# Connectors.net
KiCad netlist of a schematic drawn in Altium Designer
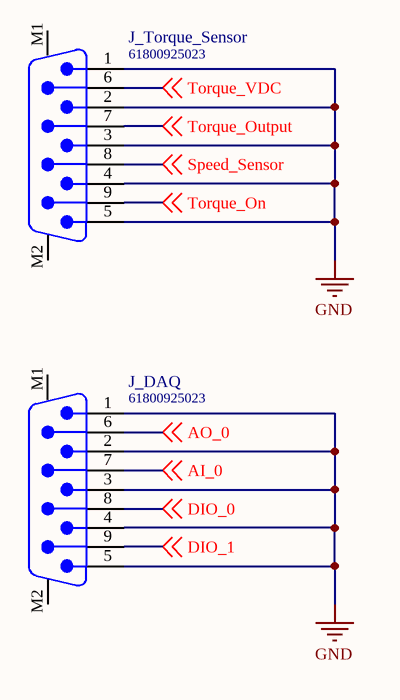
[diagram p0: Connectors.SchDoc]

(export (version "E")
  (design (tool "Eeschema 10.0.6"))
  (components
    (comp (ref "J_DAQ")
      (value "61800925023")
      (footprint "61800925023")
      (description "Male PCB Connector WR-DSUB, Vertical, 9 pins")
      (fields (field (name "MANUFACTURER") "Wurth Elektronik") (field (name "PUBLISHER") "WurthElektronik"))
      (libsource (lib "Altium Content Vault") (part "WE-CN-2S-2M-D9"))
    )
    (comp (ref "J_Torque_Sensor")
      (value "61800925023")
      (footprint "61800925023")
      (description "Male PCB Connector WR-DSUB, Vertical, 9 pins")
      (fields (field (name "MANUFACTURER") "Wurth Elektronik") (field (name "PUBLISHER") "WurthElektronik"))
      (libsource (lib "Altium Content Vault") (part "WE-CN-2S-2M-D9"))
    )
  )
  (nets
    (net (code "1") (name "AI_0") (class "Default")
      (node (ref "J_DAQ") (pin "7") (pinfunction "7_7") (pintype "passive"))
    )
    (net (code "2") (name "AO_0") (class "Default")
      (node (ref "J_DAQ") (pin "6") (pinfunction "6_6") (pintype "passive"))
    )
    (net (code "3") (name "DIO_0") (class "Default")
      (node (ref "J_DAQ") (pin "8") (pinfunction "8_8") (pintype "passive"))
    )
    (net (code "4") (name "DIO_1") (class "Default")
      (node (ref "J_DAQ") (pin "9") (pinfunction "9_9") (pintype "passive"))
    )
    (net (code "5") (name "GND") (class "Default")
      (node (ref "J_DAQ") (pin "1") (pinfunction "1_1") (pintype "passive"))
      (node (ref "J_DAQ") (pin "2") (pinfunction "2_2") (pintype "passive"))
      (node (ref "J_DAQ") (pin "3") (pinfunction "3_3") (pintype "passive"))
      (node (ref "J_DAQ") (pin "4") (pinfunction "4_4") (pintype "passive"))
      (node (ref "J_DAQ") (pin "5") (pinfunction "5_5") (pintype "passive"))
      (node (ref "J_Torque_Sensor") (pin "1") (pinfunction "1_1") (pintype "passive"))
      (node (ref "J_Torque_Sensor") (pin "2") (pinfunction "2_2") (pintype "passive"))
      (node (ref "J_Torque_Sensor") (pin "3") (pinfunction "3_3") (pintype "passive"))
      (node (ref "J_Torque_Sensor") (pin "4") (pinfunction "4_4") (pintype "passive"))
      (node (ref "J_Torque_Sensor") (pin "5") (pinfunction "5_5") (pintype "passive"))
    )
    (net (code "6") (name "Speed_Sensor") (class "Default")
      (node (ref "J_Torque_Sensor") (pin "8") (pinfunction "8_8") (pintype "passive"))
    )
    (net (code "7") (name "Torque_On") (class "Default")
      (node (ref "J_Torque_Sensor") (pin "9") (pinfunction "9_9") (pintype "passive"))
    )
    (net (code "8") (name "Torque_Output") (class "Default")
      (node (ref "J_Torque_Sensor") (pin "7") (pinfunction "7_7") (pintype "passive"))
    )
    (net (code "9") (name "Torque_VDC") (class "Default")
      (node (ref "J_Torque_Sensor") (pin "6") (pinfunction "6_6") (pintype "passive"))
    )
    (net (code "10") (name "unconnected-(J_DAQ-PadM1)") (class "Default")
      (node (ref "J_DAQ") (pin "M1") (pinfunction "M1_M1") (pintype "passive"))
    )
    (net (code "11") (name "unconnected-(J_DAQ-PadM2)") (class "Default")
      (node (ref "J_DAQ") (pin "M2") (pinfunction "M2_M2") (pintype "passive"))
    )
    (net (code "12") (name "unconnected-(J_Torque_Sensor-PadM1)") (class "Default")
      (node (ref "J_Torque_Sensor") (pin "M1") (pinfunction "M1_M1") (pintype "passive"))
    )
    (net (code "13") (name "unconnected-(J_Torque_Sensor-PadM2)") (class "Default")
      (node (ref "J_Torque_Sensor") (pin "M2") (pinfunction "M2_M2") (pintype "passive"))
    )
  )
)
